# CATS-FAT-USB.net
KiCad netlist of a schematic drawn in Altium Designer
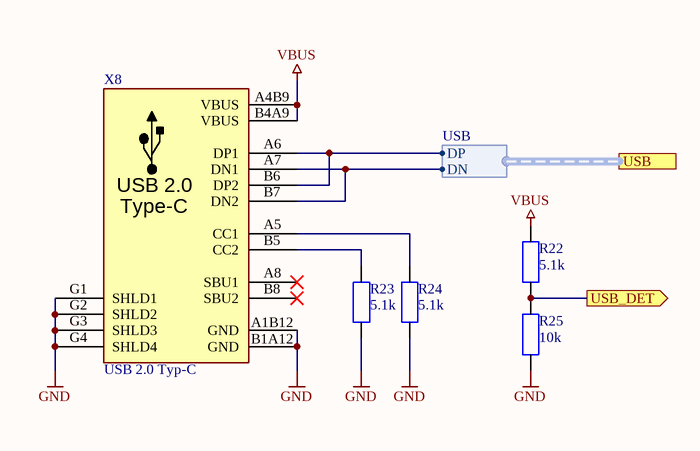
[diagram p0: CATS-FAT-USB.SchDoc]

(export (version "E")
  (design (tool "Eeschema 10.0.6"))
  (components
    (comp (ref "R22")
      (value "5.1k")
      (footprint "SMD Widerstand 0603")
      (description "SMD Chip Resistor E24")
      (libsource (lib "") (part "E24 - 5.1k_1"))
    )
    (comp (ref "R23")
      (value "5.1k")
      (footprint "SMD Widerstand 0603")
      (description "SMD Chip Resistor E24")
      (libsource (lib "Resistors-E24") (part "E24 - 5.1k"))
    )
    (comp (ref "R24")
      (value "5.1k")
      (footprint "SMD Widerstand 0603")
      (description "SMD Chip Resistor E24")
      (libsource (lib "Resistors-E24") (part "E24 - 5.1k"))
    )
    (comp (ref "R25")
      (value "10k")
      (footprint "SMD Widerstand 0603")
      (description "SMD Chip Resistor E24")
      (libsource (lib "Resistors-E24") (part "E24 - 10k"))
    )
    (comp (ref "X8")
      (value "USB 2.0 Typ-C")
      (footprint "THT USB-C Socket (A40-00119)")
      (description "Typ-C")
      (libsource (lib "Connectors") (part "USB Type-C USB 2.0"))
    )
  )
  (nets
    (net (code "2") (name "/USB_DET") (class "Default")
      (node (ref "R22") (pin "2") (pinfunction "2_2") (pintype "passive"))
      (node (ref "R25") (pin "1") (pinfunction "1_1") (pintype "passive"))
    )
    (net (code "4") (name "GND") (class "Default")
      (node (ref "R23") (pin "1") (pinfunction "1_1") (pintype "passive"))
      (node (ref "R24") (pin "1") (pinfunction "1_1") (pintype "passive"))
      (node (ref "R25") (pin "2") (pinfunction "2_2") (pintype "passive"))
      (node (ref "X8") (pin "A1B12") (pinfunction "GND_A1B12") (pintype "passive"))
      (node (ref "X8") (pin "B1A12") (pinfunction "GND_B1A12") (pintype "passive"))
      (node (ref "X8") (pin "G1") (pinfunction "SHLD1_G1") (pintype "passive"))
      (node (ref "X8") (pin "G2") (pinfunction "SHLD2_G2") (pintype "passive"))
      (node (ref "X8") (pin "G3") (pinfunction "SHLD3_G3") (pintype "passive"))
      (node (ref "X8") (pin "G4") (pinfunction "SHLD4_G4") (pintype "passive"))
    )
    (net (code "5") (name "Net-(X8-CC1)") (class "Default")
      (node (ref "R24") (pin "2") (pinfunction "2_2") (pintype "passive"))
      (node (ref "X8") (pin "A5") (pinfunction "CC1_A5") (pintype "passive"))
    )
    (net (code "6") (name "Net-(X8-CC2)") (class "Default")
      (node (ref "R23") (pin "2") (pinfunction "2_2") (pintype "passive"))
      (node (ref "X8") (pin "B5") (pinfunction "CC2_B5") (pintype "passive"))
    )
    (net (code "7") (name "Net-(X8-DN1)") (class "Default")
      (node (ref "X8") (pin "A7") (pinfunction "DN1_A7") (pintype "passive"))
      (node (ref "X8") (pin "B7") (pinfunction "DN2_B7") (pintype "passive"))
    )
    (net (code "8") (name "Net-(X8-DP1)") (class "Default")
      (node (ref "X8") (pin "A6") (pinfunction "DP1_A6") (pintype "passive"))
      (node (ref "X8") (pin "B6") (pinfunction "DP2_B6") (pintype "passive"))
    )
    (net (code "9") (name "VBUS") (class "Default")
      (node (ref "R22") (pin "1") (pinfunction "1_1") (pintype "passive"))
      (node (ref "X8") (pin "A4B9") (pinfunction "VBUS_A4B9") (pintype "passive"))
      (node (ref "X8") (pin "B4A9") (pinfunction "VBUS_B4A9") (pintype "passive"))
    )
    (net (code "10") (name "unconnected-(X8-SBU1-PadA8)") (class "Default")
      (node (ref "X8") (pin "A8") (pinfunction "SBU1_A8") (pintype "passive+no_connect"))
    )
    (net (code "11") (name "unconnected-(X8-SBU2-PadB8)") (class "Default")
      (node (ref "X8") (pin "B8") (pinfunction "SBU2_B8") (pintype "passive+no_connect"))
    )
  )
)
